# adc_dac_txmix.net
KiCad netlist of a schematic drawn in Altium Designer
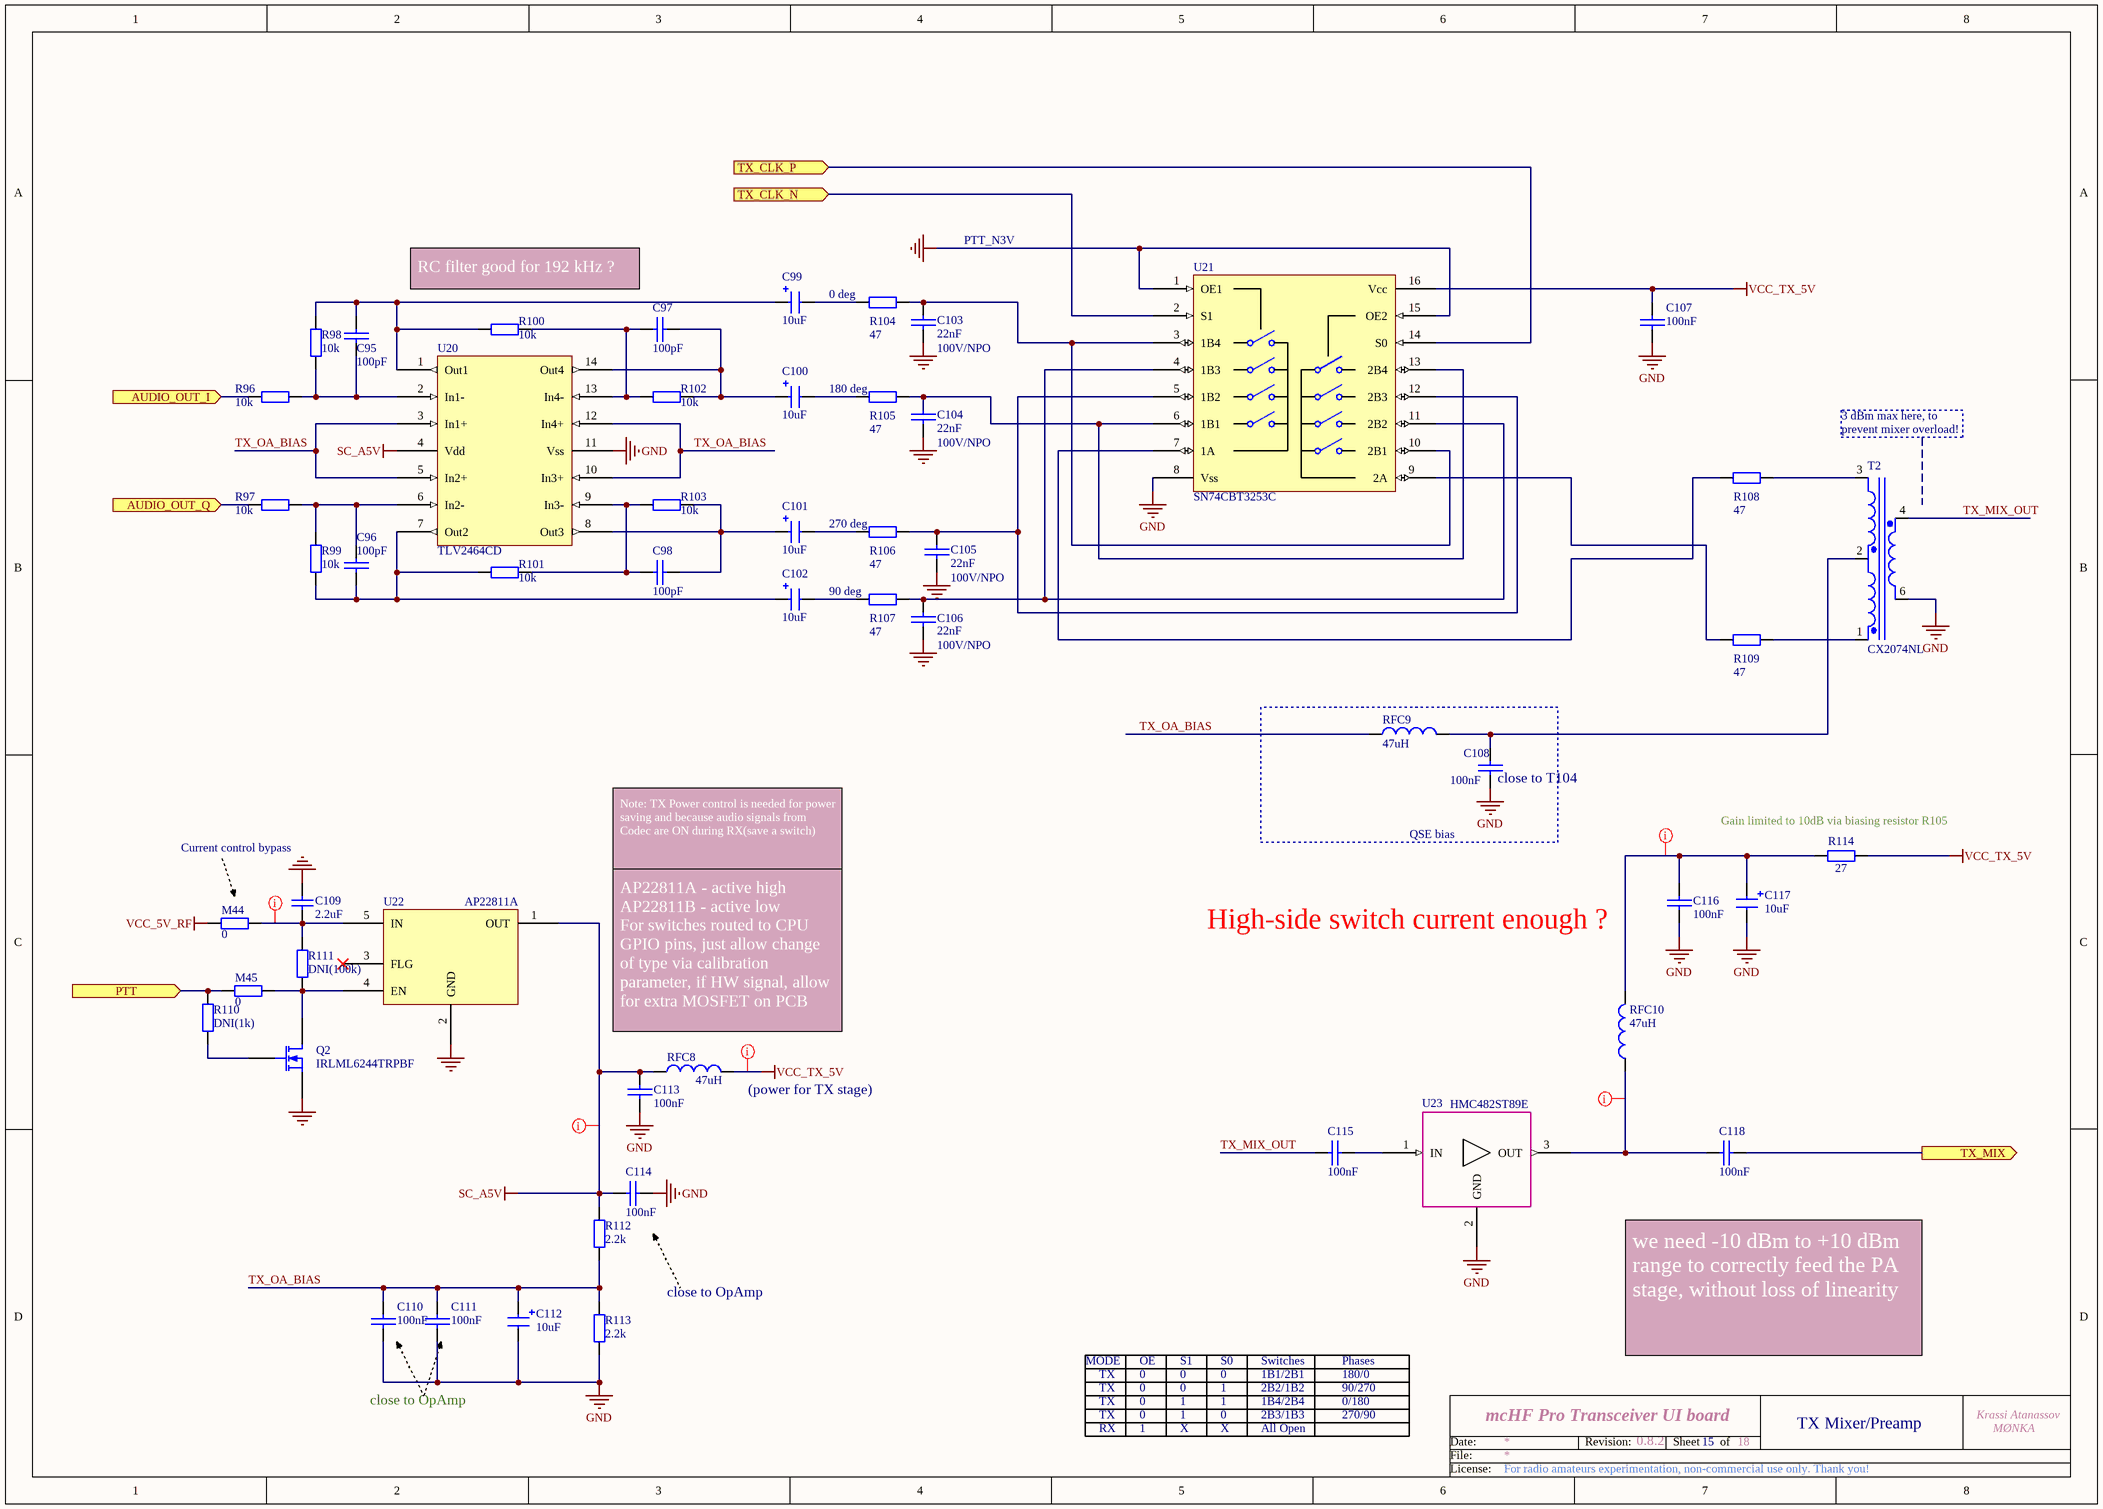
[diagram p0: adc_dac_txmix.SchDoc]

(export (version "E")
  (design (tool "Eeschema 10.0.6"))
  (components
    (comp (ref "C95")
      (value "100pF")
      (footprint "0805")
      (description "Capacitor")
      (libsource (lib "mcHF_rf") (part "CAP"))
    )
    (comp (ref "C96")
      (value "100pF")
      (footprint "0805")
      (description "Capacitor")
      (libsource (lib "mcHF_rf") (part "CAP"))
    )
    (comp (ref "C97")
      (value "100pF")
      (footprint "0805")
      (description "Capacitor")
      (libsource (lib "mcHF_rf") (part "CAP"))
    )
    (comp (ref "C98")
      (value "100pF")
      (footprint "0805")
      (description "Capacitor")
      (libsource (lib "mcHF_rf") (part "CAP"))
    )
    (comp (ref "C99")
      (value "10uF")
      (footprint "1206_Elec_Cap")
      (description "Electrolitic capacitor")
      (libsource (lib "mcHF_rf") (part "CAP-POL"))
    )
    (comp (ref "C100")
      (value "10uF")
      (footprint "1206_Elec_Cap")
      (description "Electrolitic capacitor")
      (libsource (lib "mcHF_rf") (part "CAP-POL"))
    )
    (comp (ref "C101")
      (value "10uF")
      (footprint "1206_Elec_Cap")
      (description "Electrolitic capacitor")
      (libsource (lib "mcHF_rf") (part "CAP-POL"))
    )
    (comp (ref "C102")
      (value "10uF")
      (footprint "1206_Elec_Cap")
      (description "Electrolitic capacitor")
      (libsource (lib "mcHF_rf") (part "CAP-POL"))
    )
    (comp (ref "C103")
      (value "22nF")
      (footprint "CAP_B")
      (description "Capacitor")
      (fields (field (name "VOLTAGE") "100V/NPO"))
      (libsource (lib "mcHF_rf") (part "CAP"))
    )
    (comp (ref "C104")
      (value "22nF")
      (footprint "CAP_B")
      (description "Capacitor")
      (fields (field (name "VOLTAGE") "100V/NPO"))
      (libsource (lib "mcHF_rf") (part "CAP"))
    )
    (comp (ref "C105")
      (value "22nF")
      (footprint "CAP_B")
      (description "Capacitor")
      (fields (field (name "VOLTAGE") "100V/NPO"))
      (libsource (lib "mcHF_rf") (part "CAP"))
    )
    (comp (ref "C106")
      (value "22nF")
      (footprint "CAP_B")
      (description "Capacitor")
      (fields (field (name "VOLTAGE") "100V/NPO"))
      (libsource (lib "mcHF_rf") (part "CAP"))
    )
    (comp (ref "C107")
      (value "100nF")
      (footprint "0805")
      (description "Capacitor")
      (libsource (lib "mcHF_rf") (part "CAP"))
    )
    (comp (ref "C108")
      (value "100nF")
      (footprint "0805")
      (description "Capacitor")
      (libsource (lib "mcHF_rf") (part "CAP"))
    )
    (comp (ref "C109")
      (value "2.2uF")
      (footprint "0805")
      (description "0603  X5R 1礔")
      (fields (field (name "TOLERANCE") "10%"))
      (libsource (lib "MB963_1") (part "CAP SMD 0603  X5R 1礔 25V 10%"))
    )
    (comp (ref "C110")
      (value "100nF")
      (footprint "0805")
      (description "Capacitor")
      (libsource (lib "mcHF_rf") (part "CAP"))
    )
    (comp (ref "C111")
      (value "100nF")
      (footprint "0805")
      (description "Capacitor")
      (libsource (lib "mcHF_rf") (part "CAP"))
    )
    (comp (ref "C112")
      (value "10uF")
      (footprint "1206_Elec_Cap")
      (description "Electrolitic capacitor")
      (libsource (lib "mcHF_rf") (part "CAP-POL"))
    )
    (comp (ref "C113")
      (value "100nF")
      (footprint "0805")
      (description "Capacitor")
      (libsource (lib "mcHF_rf") (part "CAP"))
    )
    (comp (ref "C114")
      (value "100nF")
      (footprint "0805")
      (description "Capacitor")
      (libsource (lib "mcHF_rf") (part "CAP"))
    )
    (comp (ref "C115")
      (value "100nF")
      (footprint "0805")
      (description "Capacitor")
      (libsource (lib "*") (part "CAP"))
    )
    (comp (ref "C116")
      (value "100nF")
      (footprint "0805")
      (description "Capacitor")
      (libsource (lib "*") (part "CAP"))
    )
    (comp (ref "C117")
      (value "10uF")
      (footprint "1206_Elec_Cap")
      (description "Electrolitic capacitor")
      (libsource (lib "mcHF_rf") (part "CAP-POL"))
    )
    (comp (ref "C118")
      (value "100nF")
      (footprint "0805")
      (description "Capacitor")
      (libsource (lib "*") (part "CAP"))
    )
    (comp (ref "M44")
      (value "0")
      (footprint "0805")
      (description "Resistor")
      (libsource (lib "mcHF_rf") (part "RES"))
    )
    (comp (ref "M45")
      (value "0")
      (footprint "0805")
      (description "Resistor")
      (libsource (lib "") (part "RES_1"))
    )
    (comp (ref "Q2")
      (value "IRLML6244TRPBF")
      (footprint "SOT-23")
      (description "N-Channel MOSFET")
      (libsource (lib "mcHF_ui_b") (part "MOSFET-N"))
    )
    (comp (ref "R96")
      (value "10k")
      (footprint "0805")
      (description "Resistor")
      (libsource (lib "mcHF_rf") (part "RES"))
    )
    (comp (ref "R97")
      (value "10k")
      (footprint "0805")
      (description "Resistor")
      (libsource (lib "mcHF_rf") (part "RES"))
    )
    (comp (ref "R98")
      (value "10k")
      (footprint "0805")
      (description "Resistor")
      (libsource (lib "") (part "RES_2"))
    )
    (comp (ref "R99")
      (value "10k")
      (footprint "0805")
      (description "Resistor")
      (libsource (lib "") (part "RES_2"))
    )
    (comp (ref "R100")
      (value "10k")
      (footprint "0805")
      (description "Resistor")
      (libsource (lib "mcHF_rf") (part "RES"))
    )
    (comp (ref "R101")
      (value "10k")
      (footprint "0805")
      (description "Resistor")
      (libsource (lib "mcHF_rf") (part "RES"))
    )
    (comp (ref "R102")
      (value "10k")
      (footprint "0805")
      (description "Resistor")
      (libsource (lib "mcHF_rf") (part "RES"))
    )
    (comp (ref "R103")
      (value "10k")
      (footprint "0805")
      (description "Resistor")
      (libsource (lib "mcHF_rf") (part "RES"))
    )
    (comp (ref "R104")
      (value "47")
      (footprint "0805")
      (description "Resistor")
      (libsource (lib "mcHF_rf") (part "RES"))
    )
    (comp (ref "R105")
      (value "47")
      (footprint "0805")
      (description "Resistor")
      (libsource (lib "mcHF_rf") (part "RES"))
    )
    (comp (ref "R106")
      (value "47")
      (footprint "0805")
      (description "Resistor")
      (libsource (lib "mcHF_rf") (part "RES"))
    )
    (comp (ref "R107")
      (value "47")
      (footprint "0805")
      (description "Resistor")
      (libsource (lib "mcHF_rf") (part "RES"))
    )
    (comp (ref "R108")
      (value "47")
      (footprint "0805")
      (description "Resistor")
      (libsource (lib "mcHF_rf") (part "RES"))
    )
    (comp (ref "R109")
      (value "47")
      (footprint "0805")
      (description "Resistor")
      (libsource (lib "mcHF_rf") (part "RES"))
    )
    (comp (ref "R110")
      (value "DNI(1k)")
      (footprint "0805")
      (description "Resistor")
      (libsource (lib "") (part "RES_2"))
    )
    (comp (ref "R111")
      (value "DNI(100k)")
      (footprint "0805")
      (description "Resistor")
      (libsource (lib "mcHF_ui") (part "RES"))
    )
    (comp (ref "R112")
      (value "2.2k")
      (footprint "0805")
      (description "Resistor")
      (libsource (lib "") (part "RES_2"))
    )
    (comp (ref "R113")
      (value "2.2k")
      (footprint "0805")
      (description "Resistor")
      (libsource (lib "") (part "RES_2"))
    )
    (comp (ref "R114")
      (value "27")
      (footprint "1206")
      (description "Resistor")
      (libsource (lib "") (part "RES_1"))
    )
    (comp (ref "RFC8")
      (value "47uH")
      (footprint "0805")
      (description "INDUCTOR, SIGNAL LINE, 4.7UH, 1005")
      (libsource (lib "mcHF_rf") (part "TDK-NLV25T"))
    )
    (comp (ref "RFC9")
      (value "47uH")
      (footprint "0805")
      (description "INDUCTOR, SIGNAL LINE, 4.7UH, 1005")
      (libsource (lib "mcHF_rf") (part "TDK-NLV25T"))
    )
    (comp (ref "RFC10")
      (value "47uH")
      (footprint "0805")
      (description "INDUCTOR, SIGNAL LINE, 4.7UH, 1005")
      (libsource (lib "mcHF_rf") (part "TDK-NLV25T"))
    )
    (comp (ref "T2")
      (value "CX2074NL")
      (footprint "SOP5_NEW1")
      (description "Wideband RF Transformer 1:4")
      (libsource (lib "mcHF_rf") (part "CX2074NL"))
    )
    (comp (ref "U20")
      (value "TLV2464CD")
      (footprint "SO-14-Pro")
      (description "Low Power, Rail-To-Rail OpAmp")
      (libsource (lib "mcHF_rf") (part "TLV2464CD"))
    )
    (comp (ref "U21")
      (value "SN74CBT3253C")
      (footprint "SO-16-Pro")
      (description "Dual 4:1 Demux/Analog Switch")
      (libsource (lib "mcHF_rf") (part "SN74CBT3253C"))
    )
    (comp (ref "U22")
      (value "AP22811A")
      (footprint "SOT25-5")
      (description "High-side switch")
      (libsource (lib "__ui") (part "AP22811"))
    )
    (comp (ref "U23")
      (value "HMC482ST89E")
      (footprint "SOT89L_new")
      (description "MMIC AMPLIFIER")
      (libsource (lib "mcHF_rf") (part "HMS482ST89E"))
    )
  )
  (nets
    (net (code "1") (name "/AUDIO_OUT_I") (class "Default")
      (node (ref "R96") (pin "1") (pinfunction "1_1") (pintype "passive"))
    )
    (net (code "2") (name "/AUDIO_OUT_Q") (class "Default")
      (node (ref "R97") (pin "1") (pinfunction "1_1") (pintype "passive"))
    )
    (net (code "3") (name "/PTT") (class "Default")
      (node (ref "M45") (pin "2") (pinfunction "2_2") (pintype "passive"))
      (node (ref "R110") (pin "2") (pinfunction "2_2") (pintype "passive"))
    )
    (net (code "4") (name "/TX_CLK_N") (class "Default")
      (node (ref "U21") (pin "2") (pinfunction "S1_2") (pintype "input"))
    )
    (net (code "5") (name "/TX_CLK_P") (class "Default")
      (node (ref "U21") (pin "14") (pinfunction "S0_14") (pintype "input"))
    )
    (net (code "6") (name "/TX_MIX") (class "Default")
      (node (ref "C118") (pin "1") (pinfunction "1_1") (pintype "passive"))
    )
    (net (code "7") (name "/TX_MIX_OUT") (class "Default")
      (node (ref "C115") (pin "2") (pinfunction "2_2") (pintype "passive"))
      (node (ref "T2") (pin "4") (pinfunction "Pri-_4") (pintype "passive"))
    )
    (net (code "8") (name "/TX_OA_BIAS") (class "Default")
      (node (ref "C110") (pin "2") (pinfunction "2_2") (pintype "passive"))
      (node (ref "C111") (pin "2") (pinfunction "2_2") (pintype "passive"))
      (node (ref "C112") (pin "1") (pinfunction "1_1") (pintype "passive"))
      (node (ref "R112") (pin "1") (pinfunction "1_1") (pintype "passive"))
      (node (ref "R113") (pin "2") (pinfunction "2_2") (pintype "passive"))
      (node (ref "RFC9") (pin "1") (pinfunction "1_1") (pintype "passive"))
      (node (ref "U20") (pin "10") (pinfunction "In3+_10") (pintype "input"))
      (node (ref "U20") (pin "12") (pinfunction "In4+_12") (pintype "input"))
      (node (ref "U20") (pin "3") (pinfunction "In1+_3") (pintype "input"))
      (node (ref "U20") (pin "5") (pinfunction "In2+_5") (pintype "input"))
    )
    (net (code "9") (name "GND") (class "Default")
      (node (ref "C103") (pin "2") (pinfunction "2_2") (pintype "passive"))
      (node (ref "C104") (pin "2") (pinfunction "2_2") (pintype "passive"))
      (node (ref "C105") (pin "2") (pinfunction "2_2") (pintype "passive"))
      (node (ref "C106") (pin "2") (pinfunction "2_2") (pintype "passive"))
      (node (ref "C107") (pin "1") (pinfunction "1_1") (pintype "passive"))
      (node (ref "C108") (pin "1") (pinfunction "1_1") (pintype "passive"))
      (node (ref "C109") (pin "1") (pinfunction "1_1") (pintype "passive"))
      (node (ref "C110") (pin "1") (pinfunction "1_1") (pintype "passive"))
      (node (ref "C111") (pin "1") (pinfunction "1_1") (pintype "passive"))
      (node (ref "C112") (pin "2") (pinfunction "2_2") (pintype "passive"))
      (node (ref "C113") (pin "1") (pinfunction "1_1") (pintype "passive"))
      (node (ref "C114") (pin "1") (pinfunction "1_1") (pintype "passive"))
      (node (ref "C116") (pin "2") (pinfunction "2_2") (pintype "passive"))
      (node (ref "C117") (pin "2") (pinfunction "2_2") (pintype "passive"))
      (node (ref "Q2") (pin "2") (pinfunction "S_2") (pintype "passive"))
      (node (ref "R113") (pin "1") (pinfunction "1_1") (pintype "passive"))
      (node (ref "T2") (pin "6") (pinfunction "Pri+_6") (pintype "passive"))
      (node (ref "U20") (pin "11") (pinfunction "Vss_11") (pintype "power_in"))
      (node (ref "U21") (pin "1") (pinfunction "OE1_1") (pintype "input"))
      (node (ref "U21") (pin "15") (pinfunction "OE2_15") (pintype "input"))
      (node (ref "U21") (pin "8") (pinfunction "Vss_8") (pintype "power_in"))
      (node (ref "U22") (pin "2") (pinfunction "GND_2") (pintype "passive"))
      (node (ref "U23") (pin "2") (pinfunction "GND_2") (pintype "power_in"))
    )
    (net (code "10") (name "Net-(C99-Pad2)") (class "Default")
      (node (ref "C99") (pin "2") (pinfunction "2_2") (pintype "passive"))
      (node (ref "R104") (pin "1") (pinfunction "1_1") (pintype "passive"))
    )
    (net (code "11") (name "Net-(C100-Pad2)") (class "Default")
      (node (ref "C100") (pin "2") (pinfunction "2_2") (pintype "passive"))
      (node (ref "R105") (pin "1") (pinfunction "1_1") (pintype "passive"))
    )
    (net (code "12") (name "Net-(C101-Pad2)") (class "Default")
      (node (ref "C101") (pin "2") (pinfunction "2_2") (pintype "passive"))
      (node (ref "R106") (pin "1") (pinfunction "1_1") (pintype "passive"))
    )
    (net (code "13") (name "Net-(C102-Pad2)") (class "Default")
      (node (ref "C102") (pin "2") (pinfunction "2_2") (pintype "passive"))
      (node (ref "R107") (pin "1") (pinfunction "1_1") (pintype "passive"))
    )
    (net (code "14") (name "Net-(C116-Pad1)") (class "Default")
      (node (ref "C116") (pin "1") (pinfunction "1_1") (pintype "passive"))
      (node (ref "C117") (pin "1") (pinfunction "1_1") (pintype "passive"))
      (node (ref "R114") (pin "2") (pinfunction "2_2") (pintype "passive"))
      (node (ref "RFC10") (pin "2") (pinfunction "2_2") (pintype "passive"))
    )
    (net (code "15") (name "Net-(Q2-D)") (class "Default")
      (node (ref "M45") (pin "1") (pinfunction "1_1") (pintype "passive"))
      (node (ref "Q2") (pin "3") (pinfunction "D_3") (pintype "passive"))
      (node (ref "R111") (pin "2") (pinfunction "2_2") (pintype "passive"))
      (node (ref "U22") (pin "4") (pinfunction "EN_4") (pintype "passive"))
    )
    (net (code "16") (name "Net-(Q2-G)") (class "Default")
      (node (ref "Q2") (pin "1") (pinfunction "G_1") (pintype "passive"))
      (node (ref "R110") (pin "1") (pinfunction "1_1") (pintype "passive"))
    )
    (net (code "17") (name "Net-(T2-Sec0)") (class "Default")
      (node (ref "R109") (pin "2") (pinfunction "2_2") (pintype "passive"))
      (node (ref "T2") (pin "1") (pinfunction "Sec0_1") (pintype "passive"))
    )
    (net (code "18") (name "Net-(T2-Sec180)") (class "Default")
      (node (ref "R108") (pin "2") (pinfunction "2_2") (pintype "passive"))
      (node (ref "T2") (pin "3") (pinfunction "Sec180_3") (pintype "passive"))
    )
    (net (code "19") (name "Net-(T2-SecCmn)") (class "Default")
      (node (ref "C108") (pin "2") (pinfunction "2_2") (pintype "passive"))
      (node (ref "RFC9") (pin "2") (pinfunction "2_2") (pintype "passive"))
      (node (ref "T2") (pin "2") (pinfunction "SecCmn_2") (pintype "passive"))
    )
    (net (code "20") (name "Net-(U20-In1-)") (class "Default")
      (node (ref "C95") (pin "1") (pinfunction "1_1") (pintype "passive"))
      (node (ref "R96") (pin "2") (pinfunction "2_2") (pintype "passive"))
      (node (ref "R98") (pin "1") (pinfunction "1_1") (pintype "passive"))
      (node (ref "U20") (pin "2") (pinfunction "In1-_2") (pintype "input"))
    )
    (net (code "21") (name "Net-(U20-In2-)") (class "Default")
      (node (ref "C96") (pin "2") (pinfunction "2_2") (pintype "passive"))
      (node (ref "R97") (pin "2") (pinfunction "2_2") (pintype "passive"))
      (node (ref "R99") (pin "2") (pinfunction "2_2") (pintype "passive"))
      (node (ref "U20") (pin "6") (pinfunction "In2-_6") (pintype "input"))
    )
    (net (code "22") (name "Net-(U20-In3-)") (class "Default")
      (node (ref "C98") (pin "2") (pinfunction "2_2") (pintype "passive"))
      (node (ref "R101") (pin "2") (pinfunction "2_2") (pintype "passive"))
      (node (ref "R103") (pin "1") (pinfunction "1_1") (pintype "passive"))
      (node (ref "U20") (pin "9") (pinfunction "In3-_9") (pintype "input"))
    )
    (net (code "23") (name "Net-(U20-In4-)") (class "Default")
      (node (ref "C97") (pin "2") (pinfunction "2_2") (pintype "passive"))
      (node (ref "R100") (pin "2") (pinfunction "2_2") (pintype "passive"))
      (node (ref "R102") (pin "1") (pinfunction "1_1") (pintype "passive"))
      (node (ref "U20") (pin "13") (pinfunction "In4-_13") (pintype "input"))
    )
    (net (code "24") (name "Net-(U20-Out1)") (class "Default")
      (node (ref "C95") (pin "2") (pinfunction "2_2") (pintype "passive"))
      (node (ref "C99") (pin "1") (pinfunction "1_1") (pintype "passive"))
      (node (ref "R100") (pin "1") (pinfunction "1_1") (pintype "passive"))
      (node (ref "R98") (pin "2") (pinfunction "2_2") (pintype "passive"))
      (node (ref "U20") (pin "1") (pinfunction "Out1_1") (pintype "output"))
    )
    (net (code "25") (name "Net-(U20-Out2)") (class "Default")
      (node (ref "C102") (pin "1") (pinfunction "1_1") (pintype "passive"))
      (node (ref "C96") (pin "1") (pinfunction "1_1") (pintype "passive"))
      (node (ref "R101") (pin "1") (pinfunction "1_1") (pintype "passive"))
      (node (ref "R99") (pin "1") (pinfunction "1_1") (pintype "passive"))
      (node (ref "U20") (pin "7") (pinfunction "Out2_7") (pintype "output"))
    )
    (net (code "26") (name "Net-(U20-Out3)") (class "Default")
      (node (ref "C101") (pin "1") (pinfunction "1_1") (pintype "passive"))
      (node (ref "C98") (pin "1") (pinfunction "1_1") (pintype "passive"))
      (node (ref "R103") (pin "2") (pinfunction "2_2") (pintype "passive"))
      (node (ref "U20") (pin "8") (pinfunction "Out3_8") (pintype "output"))
    )
    (net (code "27") (name "Net-(U20-Out4)") (class "Default")
      (node (ref "C100") (pin "1") (pinfunction "1_1") (pintype "passive"))
      (node (ref "C97") (pin "1") (pinfunction "1_1") (pintype "passive"))
      (node (ref "R102") (pin "2") (pinfunction "2_2") (pintype "passive"))
      (node (ref "U20") (pin "14") (pinfunction "Out4_14") (pintype "output"))
    )
    (net (code "28") (name "Net-(U21-1A)") (class "Default")
      (node (ref "R108") (pin "1") (pinfunction "1_1") (pintype "passive"))
      (node (ref "U21") (pin "7") (pinfunction "1A_7") (pintype "bidirectional"))
    )
    (net (code "29") (name "Net-(U21-1B1)") (class "Default")
      (node (ref "C104") (pin "1") (pinfunction "1_1") (pintype "passive"))
      (node (ref "R105") (pin "2") (pinfunction "2_2") (pintype "passive"))
      (node (ref "U21") (pin "13") (pinfunction "2B4_13") (pintype "bidirectional"))
      (node (ref "U21") (pin "6") (pinfunction "1B1_6") (pintype "bidirectional"))
    )
    (net (code "30") (name "Net-(U21-1B2)") (class "Default")
      (node (ref "C105") (pin "1") (pinfunction "1_1") (pintype "passive"))
      (node (ref "R106") (pin "2") (pinfunction "2_2") (pintype "passive"))
      (node (ref "U21") (pin "12") (pinfunction "2B3_12") (pintype "bidirectional"))
      (node (ref "U21") (pin "5") (pinfunction "1B2_5") (pintype "bidirectional"))
    )
    (net (code "31") (name "Net-(U21-1B3)") (class "Default")
      (node (ref "C106") (pin "1") (pinfunction "1_1") (pintype "passive"))
      (node (ref "R107") (pin "2") (pinfunction "2_2") (pintype "passive"))
      (node (ref "U21") (pin "11") (pinfunction "2B2_11") (pintype "bidirectional"))
      (node (ref "U21") (pin "4") (pinfunction "1B3_4") (pintype "bidirectional"))
    )
    (net (code "32") (name "Net-(U21-1B4)") (class "Default")
      (node (ref "C103") (pin "1") (pinfunction "1_1") (pintype "passive"))
      (node (ref "R104") (pin "2") (pinfunction "2_2") (pintype "passive"))
      (node (ref "U21") (pin "10") (pinfunction "2B1_10") (pintype "bidirectional"))
      (node (ref "U21") (pin "3") (pinfunction "1B4_3") (pintype "bidirectional"))
    )
    (net (code "33") (name "Net-(U21-2A)") (class "Default")
      (node (ref "R109") (pin "1") (pinfunction "1_1") (pintype "passive"))
      (node (ref "U21") (pin "9") (pinfunction "2A_9") (pintype "bidirectional"))
    )
    (net (code "34") (name "Net-(U22-IN)") (class "Default")
      (node (ref "C109") (pin "2") (pinfunction "2_2") (pintype "passive"))
      (node (ref "M44") (pin "2") (pinfunction "2_2") (pintype "passive"))
      (node (ref "R111") (pin "1") (pinfunction "1_1") (pintype "passive"))
      (node (ref "U22") (pin "5") (pinfunction "IN_5") (pintype "power_in"))
    )
    (net (code "35") (name "Net-(U23-IN)") (class "Default")
      (node (ref "C115") (pin "1") (pinfunction "1_1") (pintype "passive"))
      (node (ref "U23") (pin "1") (pinfunction "IN_1") (pintype "input"))
    )
    (net (code "36") (name "Net-(U23-OUT)") (class "Default")
      (node (ref "C118") (pin "2") (pinfunction "2_2") (pintype "passive"))
      (node (ref "RFC10") (pin "1") (pinfunction "1_1") (pintype "passive"))
      (node (ref "U23") (pin "3") (pinfunction "OUT_3") (pintype "output"))
    )
    (net (code "37") (name "SC_A5V") (class "Default")
      (node (ref "C113") (pin "2") (pinfunction "2_2") (pintype "passive"))
      (node (ref "C114") (pin "2") (pinfunction "2_2") (pintype "passive"))
      (node (ref "R112") (pin "2") (pinfunction "2_2") (pintype "passive"))
      (node (ref "RFC8") (pin "1") (pinfunction "1_1") (pintype "passive"))
      (node (ref "U20") (pin "4") (pinfunction "Vdd_4") (pintype "power_in"))
      (node (ref "U22") (pin "1") (pinfunction "OUT_1") (pintype "power_in"))
    )
    (net (code "38") (name "VCC_5V_RF") (class "Default")
      (node (ref "M44") (pin "1") (pinfunction "1_1") (pintype "passive"))
    )
    (net (code "39") (name "VCC_TX_5V") (class "Default")
      (node (ref "C107") (pin "2") (pinfunction "2_2") (pintype "passive"))
      (node (ref "R114") (pin "1") (pinfunction "1_1") (pintype "passive"))
      (node (ref "RFC8") (pin "2") (pinfunction "2_2") (pintype "passive"))
      (node (ref "U21") (pin "16") (pinfunction "Vcc_16") (pintype "power_in"))
    )
    (net (code "40") (name "unconnected-(U22-FLG-Pad3)") (class "Default")
      (node (ref "U22") (pin "3") (pinfunction "FLG_3") (pintype "passive+no_connect"))
    )
  )
)
